# nguon12.net
KiCad netlist of a schematic drawn in Altium Designer
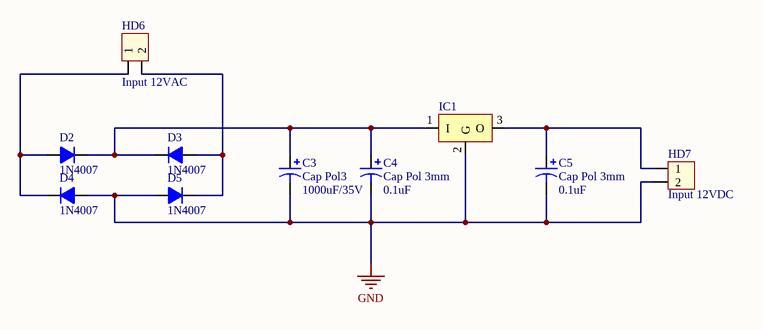
[diagram p0: nguon12.SchDoc]

(export (version "E")
  (design (tool "Eeschema 10.0.6"))
  (components
    (comp (ref "C3")
      (value "Cap Pol3")
      (footprint "CP2/5")
      (description "Polarized Capacitor (Surface Mount)")
      (fields (field (name "ALTIUM_VALUE") "1000uF/35V") (field (name "PUBLISHER") "Altium Limited"))
      (libsource (lib "syhaunguyen") (part "Cap Pol3"))
    )
    (comp (ref "C4")
      (value "Cap Pol 3mm")
      (footprint "C3MM")
      (description "Polarized Capacitor (Axial)")
      (fields (field (name "ALTIUM_UNNAMED_1") "0.1uF") (field (name "PUBLISHER") "Altium Limited"))
      (libsource (lib "My Library") (part "Cap Pol 3mm"))
    )
    (comp (ref "C5")
      (value "Cap Pol 3mm")
      (footprint "C3MM")
      (description "Polarized Capacitor (Axial)")
      (fields (field (name "ALTIUM_UNNAMED_1") "0.1uF") (field (name "PUBLISHER") "Altium Limited"))
      (libsource (lib "My Library") (part "Cap Pol 3mm"))
    )
    (comp (ref "D2")
      (value "1N4007")
      (footprint "D2A")
      (description "Diode 1A")
      (libsource (lib "syhaunguyen") (part "D1A"))
    )
    (comp (ref "D3")
      (value "1N4007")
      (footprint "D2A")
      (description "Diode 1A")
      (libsource (lib "syhaunguyen") (part "D1A"))
    )
    (comp (ref "D4")
      (value "1N4007")
      (footprint "D2A")
      (description "Diode 1A")
      (libsource (lib "syhaunguyen") (part "D1A"))
    )
    (comp (ref "D5")
      (value "1N4007")
      (footprint "D2A")
      (description "Diode 1A")
      (libsource (lib "syhaunguyen") (part "D1A"))
    )
    (comp (ref "HD6")
      (value "Input 12VAC")
      (footprint "HED2")
      (description "Header 2 (Green)")
      (libsource (lib "") (part "Hed2_1"))
    )
    (comp (ref "HD7")
      (value "Input 12VDC")
      (footprint "HED2")
      (description "Header 2 (Green)")
      (libsource (lib "My Library") (part "Hed2"))
    )
    (comp (ref "IC1")
      (value "LM78xx")
      (footprint "TO220-123")
      (description "Positive Voltage Regulator")
      (fields (field (name "PUBLISHER") "Altium Limited"))
      (libsource (lib "LIBRARY") (part "LM78xx"))
    )
  )
  (nets
    (net (code "1") (name "GND") (class "Default")
      (node (ref "C3") (pin "2") (pinfunction "2_2") (pintype "passive"))
      (node (ref "C4") (pin "2") (pinfunction "2_2") (pintype "passive"))
      (node (ref "C5") (pin "2") (pinfunction "2_2") (pintype "passive"))
      (node (ref "D4") (pin "1") (pinfunction "A_1") (pintype "passive"))
      (node (ref "D5") (pin "1") (pinfunction "A_1") (pintype "passive"))
      (node (ref "HD7") (pin "2") (pinfunction "2_2") (pintype "passive"))
      (node (ref "IC1") (pin "2") (pinfunction "G_2") (pintype "power_in"))
    )
    (net (code "2") (name "Net-(D2-A)") (class "Default")
      (node (ref "D2") (pin "1") (pinfunction "A_1") (pintype "passive"))
      (node (ref "D4") (pin "2") (pinfunction "K_2") (pintype "passive"))
      (node (ref "HD6") (pin "1") (pinfunction "1_1") (pintype "passive"))
    )
    (net (code "3") (name "Net-(D2-K)") (class "Default")
      (node (ref "C3") (pin "1") (pinfunction "1_1") (pintype "passive"))
      (node (ref "C4") (pin "1") (pinfunction "1_1") (pintype "passive"))
      (node (ref "D2") (pin "2") (pinfunction "K_2") (pintype "passive"))
      (node (ref "D3") (pin "2") (pinfunction "K_2") (pintype "passive"))
      (node (ref "IC1") (pin "1") (pinfunction "I_1") (pintype "power_in"))
    )
    (net (code "4") (name "Net-(D3-A)") (class "Default")
      (node (ref "D3") (pin "1") (pinfunction "A_1") (pintype "passive"))
      (node (ref "D5") (pin "2") (pinfunction "K_2") (pintype "passive"))
      (node (ref "HD6") (pin "2") (pinfunction "2_2") (pintype "passive"))
    )
    (net (code "5") (name "Net-(IC1-O)") (class "Default")
      (node (ref "C5") (pin "1") (pinfunction "1_1") (pintype "passive"))
      (node (ref "HD7") (pin "1") (pinfunction "1_1") (pintype "passive"))
      (node (ref "IC1") (pin "3") (pinfunction "O_3") (pintype "power_in"))
    )
  )
)
